# Custom_ST-Link_V3_0.net
KiCad netlist of a schematic drawn in Altium Designer
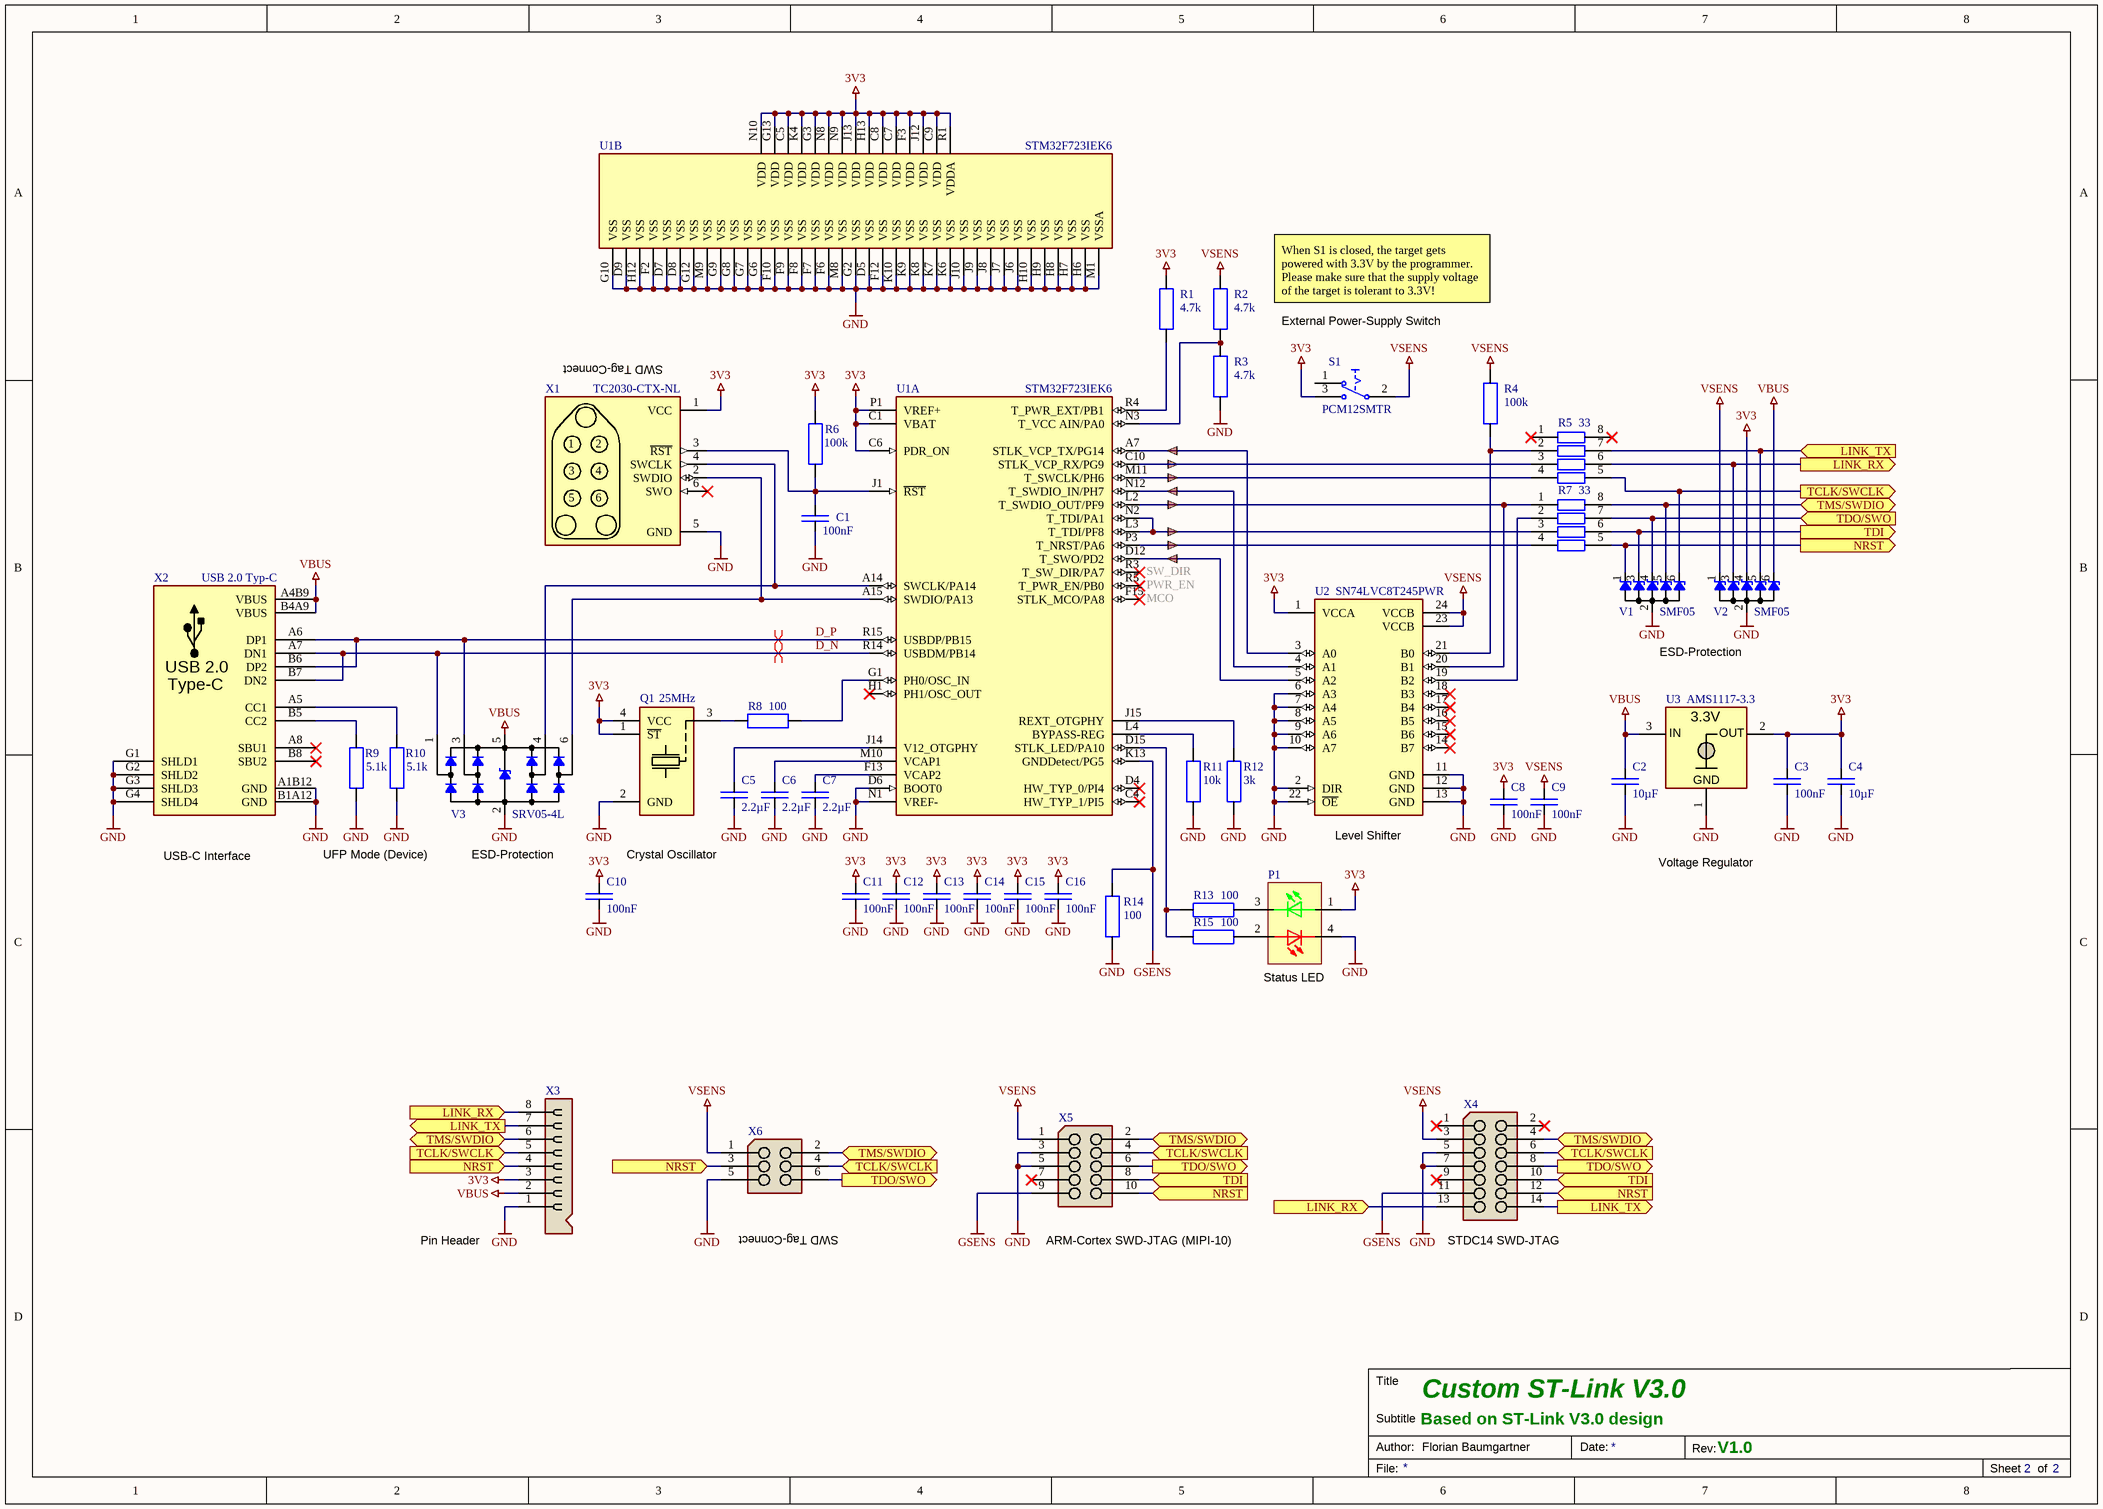
[diagram p0: Custom ST-Link V3.0.SchDoc]

(export (version "E")
  (design (tool "Eeschema 10.0.6"))
  (components
    (comp (ref "C1")
      (value "100nF")
      (footprint "SMD Keramikkondensator 0402")
      (description "CAP-MK")
      (libsource (lib "AudioAmp") (part "C-CAPACITOR"))
    )
    (comp (ref "C2")
      (value "10µF")
      (footprint "SMD Keramikkondensator 0603")
      (description "CAP-MK")
      (libsource (lib "AudioAmp") (part "C-CAPACITOR"))
    )
    (comp (ref "C3")
      (value "100nF")
      (footprint "SMD Keramikkondensator 0402")
      (description "CAP-MK")
      (libsource (lib "AudioAmp") (part "C-CAPACITOR"))
    )
    (comp (ref "C4")
      (value "10µF")
      (footprint "SMD Keramikkondensator 0603")
      (description "CAP-MK")
      (libsource (lib "AudioAmp") (part "C-CAPACITOR"))
    )
    (comp (ref "C5")
      (value "2.2µF")
      (footprint "SMD Keramikkondensator 0603")
      (description "CAP-MK")
      (libsource (lib "AudioAmp") (part "C-CAPACITOR"))
    )
    (comp (ref "C6")
      (value "2.2µF")
      (footprint "SMD Keramikkondensator 0603")
      (description "CAP-MK")
      (libsource (lib "AudioAmp") (part "C-CAPACITOR"))
    )
    (comp (ref "C7")
      (value "2.2µF")
      (footprint "SMD Keramikkondensator 0603")
      (description "CAP-MK")
      (libsource (lib "AudioAmp") (part "C-CAPACITOR"))
    )
    (comp (ref "C8")
      (value "100nF")
      (footprint "SMD Keramikkondensator 0402")
      (description "CAP-MK")
      (libsource (lib "AudioAmp") (part "C-CAPACITOR"))
    )
    (comp (ref "C9")
      (value "100nF")
      (footprint "SMD Keramikkondensator 0402")
      (description "CAP-MK")
      (libsource (lib "AudioAmp") (part "C-CAPACITOR"))
    )
    (comp (ref "C10")
      (value "100nF")
      (footprint "SMD Keramikkondensator 0402")
      (description "CAP-MK")
      (libsource (lib "AudioAmp") (part "C-CAPACITOR"))
    )
    (comp (ref "C11")
      (value "100nF")
      (footprint "SMD Keramikkondensator 0402")
      (description "CAP-MK")
      (libsource (lib "AudioAmp") (part "C-CAPACITOR"))
    )
    (comp (ref "C12")
      (value "100nF")
      (footprint "SMD Keramikkondensator 0402")
      (description "CAP-MK")
      (libsource (lib "AudioAmp") (part "C-CAPACITOR"))
    )
    (comp (ref "C13")
      (value "100nF")
      (footprint "SMD Keramikkondensator 0402")
      (description "CAP-MK")
      (libsource (lib "AudioAmp") (part "C-CAPACITOR"))
    )
    (comp (ref "C14")
      (value "100nF")
      (footprint "SMD Keramikkondensator 0402")
      (description "CAP-MK")
      (libsource (lib "AudioAmp") (part "C-CAPACITOR"))
    )
    (comp (ref "C15")
      (value "100nF")
      (footprint "SMD Keramikkondensator 0402")
      (description "CAP-MK")
      (libsource (lib "AudioAmp") (part "C-CAPACITOR"))
    )
    (comp (ref "C16")
      (value "100nF")
      (footprint "SMD Keramikkondensator 0402")
      (description "CAP-MK")
      (libsource (lib "AudioAmp") (part "C-CAPACITOR"))
    )
    (comp (ref "P1")
      (value "LTST-C155KGJRKT")
      (footprint "SMD LED 1210")
      (description "LED Red/Green")
      (libsource (lib "Custom ST-Link") (part "P-LTST-C155KGJRKT"))
    )
    (comp (ref "Q1")
      (value "25MHz")
      (footprint "SMD Crystal Oscillator 3.2X2.5X1.2")
      (description "Crystal Oscillator")
      (libsource (lib "Custom ST-Link") (part "Q-Oscillator"))
    )
    (comp (ref "R1")
      (value "4.7k")
      (footprint "SMD Widerstand 0402")
      (description "SMD-Widerstand 1/4W")
      (libsource (lib "Backplane_1") (part "R-RESISTOR"))
    )
    (comp (ref "R2")
      (value "4.7k")
      (footprint "SMD Widerstand 0402")
      (description "SMD-Widerstand 1/4W")
      (libsource (lib "Backplane_1") (part "R-RESISTOR"))
    )
    (comp (ref "R3")
      (value "4.7k")
      (footprint "SMD Widerstand 0402")
      (description "SMD-Widerstand 1/4W")
      (libsource (lib "Backplane_1") (part "R-RESISTOR"))
    )
    (comp (ref "R4")
      (value "100k")
      (footprint "SMD Widerstand 0402")
      (description "RES (E=Heizwiderstand B=Messwandler)")
      (libsource (lib "TFS Integrated Library") (part "R-RESISTOR"))
    )
    (comp (ref "R5")
      (value "33")
      (footprint "SMD Widerstand Array 4-Fach 0402")
      (description "Isolated Resistor Array")
      (libsource (lib "Custom ST-Link Old") (part "R-Array Single (4-Fach)"))
    )
    (comp (ref "R6")
      (value "100k")
      (footprint "SMD Widerstand 0402")
      (description "RES (E=Heizwiderstand B=Messwandler)")
      (libsource (lib "TFS Integrated Library") (part "R-RESISTOR"))
    )
    (comp (ref "R7")
      (value "33")
      (footprint "SMD Widerstand Array 4-Fach 0402")
      (description "Isolated Resistor Array")
      (libsource (lib "Custom ST-Link Old") (part "R-Array Single (4-Fach)"))
    )
    (comp (ref "R8")
      (value "100")
      (footprint "SMD Widerstand 0402")
      (description "SMD-Widerstand 1/4W")
      (libsource (lib "") (part "R-RESISTOR_1"))
    )
    (comp (ref "R9")
      (value "5.1k")
      (footprint "SMD Widerstand 0402")
      (description "SMD-Widerstand 1/4W")
      (libsource (lib "Backplane_1") (part "R-RESISTOR"))
    )
    (comp (ref "R10")
      (value "5.1k")
      (footprint "SMD Widerstand 0402")
      (description "SMD-Widerstand 1/4W")
      (libsource (lib "Backplane_1") (part "R-RESISTOR"))
    )
    (comp (ref "R11")
      (value "10k")
      (footprint "SMD Widerstand 0402")
      (description "RES (E=Heizwiderstand B=Messwandler)")
      (libsource (lib "TFS Integrated Library") (part "R-RESISTOR"))
    )
    (comp (ref "R12")
      (value "3k")
      (footprint "SMD Widerstand 0402")
      (description "SMD-Widerstand 1/4W")
      (libsource (lib "Backplane_1") (part "R-RESISTOR"))
    )
    (comp (ref "R13")
      (value "100")
      (footprint "SMD Widerstand 0402")
      (description "SMD-Widerstand 1/4W")
      (libsource (lib "Backplane_1") (part "R-RESISTOR"))
    )
    (comp (ref "R14")
      (value "100")
      (footprint "SMD Widerstand 0402")
      (description "SMD-Widerstand 1/4W")
      (libsource (lib "") (part "R-RESISTOR_2"))
    )
    (comp (ref "R15")
      (value "100")
      (footprint "SMD Widerstand 0402")
      (description "SMD-Widerstand 1/4W")
      (libsource (lib "Backplane_1") (part "R-RESISTOR"))
    )
    (comp (ref "S1")
      (value "PCM12SMTR")
      (footprint "SMD Switch SPDT (PCM12SMTR)")
      (description "Miniature Slide Switch")
      (libsource (lib "Custom ST-Link") (part "S-PCM12SMTR"))
    )
    (comp (ref "U1")
      (value "STM32F723IEK6")
      (description "ARM Cortex-M7 STM32F7 Microcontroller")
      (libsource (lib "Custom ST-Link") (part "U-STM32F723IEK6 (LINK V3E SWD)"))
    )
    (comp (ref "U2")
      (value "SN74LVC8T245PWR")
      (footprint "SMD IC TSSOP-24")
      (description "Octal dual supply translating transceiver")
      (libsource (lib "Custom ST-Link") (part "U-SN74LVC8T245PWR"))
    )
    (comp (ref "U3")
      (value "AMS1117-3.3")
      (footprint "SMD IC SOT-223")
      (description "LDO Voltage Regulator")
      (libsource (lib "Custom ST-Link Old") (part "T-AMS1117-3.3"))
    )
    (comp (ref "V1")
      (value "SMF05")
      (footprint "SMD IC SOT-363 (SC-70-6)")
      (description "Suppressor Diode Array")
      (libsource (lib "Custom ST-Link") (part "V-SMF05CT1G"))
    )
    (comp (ref "V2")
      (value "SMF05")
      (footprint "SMD IC SOT-363 (SC-70-6)")
      (description "Suppressor Diode Array")
      (libsource (lib "Custom ST-Link") (part "V-SMF05CT1G"))
    )
    (comp (ref "V3")
      (value "SRV05-4L")
      (footprint "SMD IC SOT-23-6")
      (description "Ultra Low Capacitance TVS Array")
      (libsource (lib "Custom ST-Link") (part "V-SRV05-4L-TP"))
    )
    (comp (ref "X1")
      (value "TC2030-CTX-NL")
      (footprint "SMD Connector TC2030-CTX-NL")
      (description "Tag-Connect for ARM-Cortex (6-Pin)")
      (libsource (lib "ZedBoard-Matrix Adapter") (part "X-TC2030-CTX-NL"))
    )
    (comp (ref "X2")
      (value "USB 2.0 Typ-C")
      (footprint "SMD USB-C Socket (A40-00119)")
      (description "Typ-C")
      (libsource (lib "Custom ST-Link") (part "X-USB-Buchse"))
    )
    (comp (ref "X3")
      (value "Buchsenleiste (8-Fach)")
      (footprint "SMD Buchsenleiste 8-Pol (1x8) 90°")
      (libsource (lib "Custom ST-Link Old") (part "X-Buchsenleiste (8-Fach)"))
    )
    (comp (ref "X4")
      (value "JTAG-Header (STDC14)")
      (footprint "SMD Connector 1.27mm (2x7)")
      (libsource (lib "Custom ST-Link Old") (part "X-JTAG-Header (STDC14)"))
    )
    (comp (ref "X5")
      (value "JTAG-Header (ARM-Cortex)")
      (footprint "SMD Connector 1.27mm (2x5)")
      (libsource (lib "Custom ST-Link Old") (part "X-JTAG-Header (ARM-Cortex)"))
    )
    (comp (ref "X6")
      (value "JTAG-Header (Tag-Connect)")
      (footprint "SMD Flachbandkabel 6-Pol Vertikal")
      (libsource (lib "Custom ST-Link Old") (part "X-JTAG-Header (Tag-Connect)"))
    )
  )
  (nets
    (net (code "1") (name "/D_N") (class "Default")
      (node (ref "U1") (pin "R14") (pinfunction "USBDM/PB14_R14") (pintype "bidirectional"))
      (node (ref "V3") (pin "1") (pinfunction "K_1") (pintype "passive"))
      (node (ref "X2") (pin "A7") (pinfunction "DN1_A7") (pintype "passive"))
      (node (ref "X2") (pin "B7") (pinfunction "DN2_B7") (pintype "passive"))
    )
    (net (code "2") (name "/D_P") (class "Default")
      (node (ref "U1") (pin "R15") (pinfunction "USBDP/PB15_R15") (pintype "bidirectional"))
      (node (ref "V3") (pin "3") (pinfunction "K_3") (pintype "passive"))
      (node (ref "X2") (pin "A6") (pinfunction "DP1_A6") (pintype "passive"))
      (node (ref "X2") (pin "B6") (pinfunction "DP2_B6") (pintype "passive"))
    )
    (net (code "3") (name "/LINK_RX") (class "Default")
      (node (ref "R5") (pin "6") (pinfunction "6_6") (pintype "passive"))
      (node (ref "V2") (pin "3") (pinfunction "K_3") (pintype "passive"))
      (node (ref "X3") (pin "8") (pinfunction "8_8") (pintype "passive"))
      (node (ref "X4") (pin "13") (pinfunction "13_13") (pintype "passive"))
    )
    (net (code "4") (name "/LINK_TX") (class "Default")
      (node (ref "R5") (pin "7") (pinfunction "7_7") (pintype "passive"))
      (node (ref "V2") (pin "5") (pinfunction "K_5") (pintype "passive"))
      (node (ref "X3") (pin "7") (pinfunction "7_7") (pintype "passive"))
      (node (ref "X4") (pin "14") (pinfunction "14_14") (pintype "passive"))
    )
    (net (code "5") (name "/NRST") (class "Default")
      (node (ref "R7") (pin "5") (pinfunction "5_5") (pintype "passive"))
      (node (ref "V1") (pin "1") (pinfunction "K_1") (pintype "passive"))
      (node (ref "X3") (pin "4") (pinfunction "4_4") (pintype "passive"))
      (node (ref "X4") (pin "12") (pinfunction "12_12") (pintype "passive"))
      (node (ref "X5") (pin "10") (pinfunction "10_10") (pintype "passive"))
      (node (ref "X6") (pin "3") (pinfunction "3_3") (pintype "passive"))
    )
    (net (code "6") (name "/TCLK{slash}SWCLK") (class "Default")
      (node (ref "R5") (pin "5") (pinfunction "5_5") (pintype "passive"))
      (node (ref "V1") (pin "6") (pinfunction "K_6") (pintype "passive"))
      (node (ref "X3") (pin "5") (pinfunction "5_5") (pintype "passive"))
      (node (ref "X4") (pin "6") (pinfunction "6_6") (pintype "passive"))
      (node (ref "X5") (pin "4") (pinfunction "4_4") (pintype "passive"))
      (node (ref "X6") (pin "4") (pinfunction "4_4") (pintype "passive"))
    )
    (net (code "7") (name "/TDI") (class "Default")
      (node (ref "R7") (pin "6") (pinfunction "6_6") (pintype "passive"))
      (node (ref "V1") (pin "3") (pinfunction "K_3") (pintype "passive"))
      (node (ref "X4") (pin "10") (pinfunction "10_10") (pintype "passive"))
      (node (ref "X5") (pin "8") (pinfunction "8_8") (pintype "passive"))
    )
    (net (code "8") (name "/TDO{slash}SWO") (class "Default")
      (node (ref "R7") (pin "7") (pinfunction "7_7") (pintype "passive"))
      (node (ref "V1") (pin "4") (pinfunction "K_4") (pintype "passive"))
      (node (ref "X4") (pin "8") (pinfunction "8_8") (pintype "passive"))
      (node (ref "X5") (pin "6") (pinfunction "6_6") (pintype "passive"))
      (node (ref "X6") (pin "6") (pinfunction "6_6") (pintype "passive"))
    )
    (net (code "9") (name "/TMS{slash}SWDIO") (class "Default")
      (node (ref "R7") (pin "8") (pinfunction "8_8") (pintype "passive"))
      (node (ref "V1") (pin "5") (pinfunction "K_5") (pintype "passive"))
      (node (ref "X3") (pin "6") (pinfunction "6_6") (pintype "passive"))
      (node (ref "X4") (pin "4") (pinfunction "4_4") (pintype "passive"))
      (node (ref "X5") (pin "2") (pinfunction "2_2") (pintype "passive"))
      (node (ref "X6") (pin "2") (pinfunction "2_2") (pintype "passive"))
    )
    (net (code "10") (name "3V3") (class "Default")
      (node (ref "C10") (pin "2") (pinfunction "2_2") (pintype "passive"))
      (node (ref "C11") (pin "2") (pinfunction "2_2") (pintype "passive"))
      (node (ref "C12") (pin "2") (pinfunction "2_2") (pintype "passive"))
      (node (ref "C13") (pin "2") (pinfunction "2_2") (pintype "passive"))
      (node (ref "C14") (pin "2") (pinfunction "2_2") (pintype "passive"))
      (node (ref "C15") (pin "2") (pinfunction "2_2") (pintype "passive"))
      (node (ref "C16") (pin "2") (pinfunction "2_2") (pintype "passive"))
      (node (ref "C3") (pin "2") (pinfunction "2_2") (pintype "passive"))
      (node (ref "C4") (pin "2") (pinfunction "2_2") (pintype "passive"))
      (node (ref "C8") (pin "2") (pinfunction "2_2") (pintype "passive"))
      (node (ref "P1") (pin "1") (pinfunction "GA_1") (pintype "passive"))
      (node (ref "Q1") (pin "1") (pinfunction "~{ST}_1") (pintype "passive"))
      (node (ref "Q1") (pin "4") (pinfunction "VCC_4") (pintype "passive"))
      (node (ref "R1") (pin "2") (pinfunction "2_2") (pintype "passive"))
      (node (ref "R6") (pin "2") (pinfunction "2_2") (pintype "passive"))
      (node (ref "S1") (pin "3") (pinfunction "NO1_3") (pintype "passive"))
      (node (ref "U1") (pin "C1") (pinfunction "VBAT_C1") (pintype "passive"))
      (node (ref "U1") (pin "C5") (pinfunction "VDD_C5") (pintype "power_in"))
      (node (ref "U1") (pin "C6") (pinfunction "PDR_ON_C6") (pintype "input"))
      (node (ref "U1") (pin "C7") (pinfunction "VDD_C7") (pintype "power_in"))
      (node (ref "U1") (pin "C8") (pinfunction "VDD_C8") (pintype "power_in"))
      (node (ref "U1") (pin "C9") (pinfunction "VDD_C9") (pintype "power_in"))
      (node (ref "U1") (pin "F3") (pinfunction "VDD_F3") (pintype "power_in"))
      (node (ref "U1") (pin "G13") (pinfunction "VDD_G13") (pintype "power_in"))
      (node (ref "U1") (pin "G3") (pinfunction "VDD_G3") (pintype "power_in"))
      (node (ref "U1") (pin "H13") (pinfunction "VDD_H13") (pintype "power_in"))
      (node (ref "U1") (pin "J12") (pinfunction "VDD_J12") (pintype "power_in"))
      (node (ref "U1") (pin "J13") (pinfunction "VDD_J13") (pintype "power_in"))
      (node (ref "U1") (pin "K4") (pinfunction "VDD_K4") (pintype "power_in"))
      (node (ref "U1") (pin "N10") (pinfunction "VDD_N10") (pintype "power_in"))
      (node (ref "U1") (pin "N8") (pinfunction "VDD_N8") (pintype "power_in"))
      (node (ref "U1") (pin "N9") (pinfunction "VDD_N9") (pintype "power_in"))
      (node (ref "U1") (pin "P1") (pinfunction "VREF+_P1") (pintype "passive"))
      (node (ref "U1") (pin "R1") (pinfunction "VDDA_R1") (pintype "power_in"))
      (node (ref "U2") (pin "1") (pinfunction "VCCA_1") (pintype "power_in"))
      (node (ref "U3") (pin "2") (pinfunction "OUT_2") (pintype "power_in"))
      (node (ref "V2") (pin "4") (pinfunction "K_4") (pintype "passive"))
      (node (ref "X1") (pin "1") (pinfunction "VCC_1") (pintype "power_in"))
      (node (ref "X3") (pin "3") (pinfunction "3_3") (pintype "passive"))
    )
    (net (code "11") (name "GND") (class "Default")
      (node (ref "C1") (pin "1") (pinfunction "1_1") (pintype "passive"))
      (node (ref "C10") (pin "1") (pinfunction "1_1") (pintype "passive"))
      (node (ref "C11") (pin "1") (pinfunction "1_1") (pintype "passive"))
      (node (ref "C12") (pin "1") (pinfunction "1_1") (pintype "passive"))
      (node (ref "C13") (pin "1") (pinfunction "1_1") (pintype "passive"))
      (node (ref "C14") (pin "1") (pinfunction "1_1") (pintype "passive"))
      (node (ref "C15") (pin "1") (pinfunction "1_1") (pintype "passive"))
      (node (ref "C16") (pin "1") (pinfunction "1_1") (pintype "passive"))
      (node (ref "C2") (pin "1") (pinfunction "1_1") (pintype "passive"))
      (node (ref "C3") (pin "1") (pinfunction "1_1") (pintype "passive"))
      (node (ref "C4") (pin "1") (pinfunction "1_1") (pintype "passive"))
      (node (ref "C5") (pin "1") (pinfunction "1_1") (pintype "passive"))
      (node (ref "C6") (pin "1") (pinfunction "1_1") (pintype "passive"))
      (node (ref "C7") (pin "1") (pinfunction "1_1") (pintype "passive"))
      (node (ref "C8") (pin "1") (pinfunction "1_1") (pintype "passive"))
      (node (ref "C9") (pin "1") (pinfunction "1_1") (pintype "passive"))
      (node (ref "P1") (pin "4") (pinfunction "RC_4") (pintype "passive"))
      (node (ref "Q1") (pin "2") (pinfunction "GND_2") (pintype "passive"))
      (node (ref "R10") (pin "1") (pinfunction "1_1") (pintype "passive"))
      (node (ref "R11") (pin "1") (pinfunction "1_1") (pintype "passive"))
      (node (ref "R12") (pin "1") (pinfunction "1_1") (pintype "passive"))
      (node (ref "R14") (pin "2") (pinfunction "2_2") (pintype "passive"))
      (node (ref "R3") (pin "1") (pinfunction "1_1") (pintype "passive"))
      (node (ref "R9") (pin "1") (pinfunction "1_1") (pintype "passive"))
      (node (ref "U1") (pin "D5") (pinfunction "VSS_D5") (pintype "power_in"))
      (node (ref "U1") (pin "D6") (pinfunction "BOOT0_D6") (pintype "input"))
      (node (ref "U1") (pin "D7") (pinfunction "VSS_D7") (pintype "power_in"))
      (node (ref "U1") (pin "D8") (pinfunction "VSS_D8") (pintype "power_in"))
      (node (ref "U1") (pin "D9") (pinfunction "VSS_D9") (pintype "power_in"))
      (node (ref "U1") (pin "F10") (pinfunction "VSS_F10") (pintype "power_in"))
      (node (ref "U1") (pin "F12") (pinfunction "VSS_F12") (pintype "power_in"))
      (node (ref "U1") (pin "F2") (pinfunction "VSS_F2") (pintype "power_in"))
      (node (ref "U1") (pin "F6") (pinfunction "VSS_F6") (pintype "power_in"))
      (node (ref "U1") (pin "F7") (pinfunction "VSS_F7") (pintype "power_in"))
      (node (ref "U1") (pin "F8") (pinfunction "VSS_F8") (pintype "power_in"))
      (node (ref "U1") (pin "F9") (pinfunction "VSS_F9") (pintype "power_in"))
      (node (ref "U1") (pin "G10") (pinfunction "VSS_G10") (pintype "power_in"))
      (node (ref "U1") (pin "G12") (pinfunction "VSS_G12") (pintype "power_in"))
      (node (ref "U1") (pin "G2") (pinfunction "VSS_G2") (pintype "power_in"))
      (node (ref "U1") (pin "G6") (pinfunction "VSS_G6") (pintype "power_in"))
      (node (ref "U1") (pin "G7") (pinfunction "VSS_G7") (pintype "power_in"))
      (node (ref "U1") (pin "G8") (pinfunction "VSS_G8") (pintype "power_in"))
      (node (ref "U1") (pin "G9") (pinfunction "VSS_G9") (pintype "power_in"))
      (node (ref "U1") (pin "H10") (pinfunction "VSS_H10") (pintype "power_in"))
      (node (ref "U1") (pin "H12") (pinfunction "VSS_H12") (pintype "power_in"))
      (node (ref "U1") (pin "H6") (pinfunction "VSS_H6") (pintype "power_in"))
      (node (ref "U1") (pin "H7") (pinfunction "VSS_H7") (pintype "power_in"))
      (node (ref "U1") (pin "H8") (pinfunction "VSS_H8") (pintype "power_in"))
      (node (ref "U1") (pin "H9") (pinfunction "VSS_H9") (pintype "power_in"))
      (node (ref "U1") (pin "J10") (pinfunction "VSS_J10") (pintype "power_in"))
      (node (ref "U1") (pin "J6") (pinfunction "VSS_J6") (pintype "power_in"))
      (node (ref "U1") (pin "J7") (pinfunction "VSS_J7") (pintype "power_in"))
      (node (ref "U1") (pin "J8") (pinfunction "VSS_J8") (pintype "power_in"))
      (node (ref "U1") (pin "J9") (pinfunction "VSS_J9") (pintype "power_in"))
      (node (ref "U1") (pin "K10") (pinfunction "VSS_K10") (pintype "power_in"))
      (node (ref "U1") (pin "K6") (pinfunction "VSS_K6") (pintype "power_in"))
      (node (ref "U1") (pin "K7") (pinfunction "VSS_K7") (pintype "power_in"))
      (node (ref "U1") (pin "K8") (pinfunction "VSS_K8") (pintype "power_in"))
      (node (ref "U1") (pin "K9") (pinfunction "VSS_K9") (pintype "power_in"))
      (node (ref "U1") (pin "M1") (pinfunction "VSSA_M1") (pintype "power_in"))
      (node (ref "U1") (pin "M8") (pinfunction "VSS_M8") (pintype "power_in"))
      (node (ref "U1") (pin "M9") (pinfunction "VSS_M9") (pintype "power_in"))
      (node (ref "U1") (pin "N1") (pinfunction "VREF-_N1") (pintype "passive"))
      (node (ref "U2") (pin "10") (pinfunction "A7_10") (pintype "bidirectional"))
      (node (ref "U2") (pin "11") (pinfunction "GND_11") (pintype "power_in"))
      (node (ref "U2") (pin "12") (pinfunction "GND_12") (pintype "power_in"))
      (node (ref "U2") (pin "13") (pinfunction "GND_13") (pintype "power_in"))
      (node (ref "U2") (pin "2") (pinfunction "DIR_2") (pintype "input"))
      (node (ref "U2") (pin "22") (pinfunction "~{OE}_22") (pintype "input"))
      (node (ref "U2") (pin "6") (pinfunction "A3_6") (pintype "bidirectional"))
      (node (ref "U2") (pin "7") (pinfunction "A4_7") (pintype "bidirectional"))
      (node (ref "U2") (pin "8") (pinfunction "A5_8") (pintype "bidirectional"))
      (node (ref "U2") (pin "9") (pinfunction "A6_9") (pintype "bidirectional"))
      (node (ref "U3") (pin "1") (pinfunction "GND_1") (pintype "power_in"))
      (node (ref "V1") (pin "2") (pinfunction "A_2") (pintype "passive"))
      (node (ref "V2") (pin "2") (pinfunction "A_2") (pintype "passive"))
      (node (ref "V3") (pin "2") (pinfunction "A_2") (pintype "passive"))
      (node (ref "X1") (pin "5") (pinfunction "GND_5") (pintype "power_in"))
      (node (ref "X2") (pin "A1B12") (pinfunction "GND_A1B12") (pintype "passive"))
      (node (ref "X2") (pin "B1A12") (pinfunction "GND_B1A12") (pintype "passive"))
      (node (ref "X2") (pin "G1") (pinfunction "SHLD1_G1") (pintype "passive"))
      (node (ref "X2") (pin "G2") (pinfunction "SHLD2_G2") (pintype "passive"))
      (node (ref "X2") (pin "G3") (pinfunction "SHLD3_G3") (pintype "passive"))
      (node (ref "X2") (pin "G4") (pinfunction "SHLD4_G4") (pintype "passive"))
      (node (ref "X3") (pin "1") (pinfunction "1_1") (pintype "passive"))
      (node (ref "X4") (pin "5") (pinfunction "5_5") (pintype "passive"))
      (node (ref "X4") (pin "7") (pinfunction "7_7") (pintype "passive"))
      (node (ref "X5") (pin "3") (pinfunction "3_3") (pintype "passive"))
      (node (ref "X5") (pin "5") (pinfunction "5_5") (pintype "passive"))
      (node (ref "X6") (pin "5") (pinfunction "5_5") (pintype "passive"))
    )
    (net (code "12") (name "GSENS") (class "Default")
      (node (ref "R14") (pin "1") (pinfunction "1_1") (pintype "passive"))
      (node (ref "U1") (pin "K13") (pinfunction "GNDDetect/PG5_K13") (pintype "bidirectional"))
      (node (ref "X4") (pin "11") (pinfunction "11_11") (pintype "passive"))
      (node (ref "X5") (pin "9") (pinfunction "9_9") (pintype "passive"))
    )
    (net (code "13") (name "Net-(P1-GC)") (class "Default")
      (node (ref "P1") (pin "3") (pinfunction "GC_3") (pintype "passive"))
      (node (ref "R13") (pin "2") (pinfunction "2_2") (pintype "passive"))
    )
    (net (code "14") (name "Net-(P1-RA)") (class "Default")
      (node (ref "P1") (pin "2") (pinfunction "RA_2") (pintype "passive"))
      (node (ref "R15") (pin "2") (pinfunction "2_2") (pintype "passive"))
    )
    (net (code "15") (name "Net-(Q1-OUT)") (class "Default")
      (node (ref "Q1") (pin "3") (pinfunction "OUT_3") (pintype "passive"))
      (node (ref "R8") (pin "2") (pinfunction "2_2") (pintype "passive"))
    )
    (net (code "16") (name "Net-(U1A-BYPASS-REG)") (class "Default")
      (node (ref "R11") (pin "2") (pinfunction "2_2") (pintype "passive"))
      (node (ref "U1") (pin "L4") (pinfunction "BYPASS-REG_L4") (pintype "passive"))
    )
    (net (code "17") (name "Net-(U1A-PH0{slash}OSC_IN)") (class "Default")
      (node (ref "R8") (pin "1") (pinfunction "1_1") (pintype "passive"))
      (node (ref "U1") (pin "G1") (pinfunction "PH0/OSC_IN_G1") (pintype "bidirectional"))
    )
    (net (code "18") (name "Net-(U1A-REXT_OTGPHY)") (class "Default")
      (node (ref "R12") (pin "2") (pinfunction "2_2") (pintype "passive"))
      (node (ref "U1") (pin "J15") (pinfunction "REXT_OTGPHY_J15") (pintype "passive"))
    )
    (net (code "19") (name "Net-(U1A-STLK_LED{slash}PA10)") (class "Default")
      (node (ref "R13") (pin "1") (pinfunction "1_1") (pintype "passive"))
      (node (ref "R15") (pin "1") (pinfunction "1_1") (pintype "passive"))
      (node (ref "U1") (pin "D15") (pinfunction "STLK_LED/PA10_D15") (pintype "bidirectional"))
    )
    (net (code "20") (name "Net-(U1A-STLK_VCP_RX{slash}PG9)") (class "Default")
      (node (ref "R5") (pin "3") (pinfunction "3_3") (pintype "passive"))
      (node (ref "U1") (pin "C10") (pinfunction "STLK_VCP_RX/PG9_C10") (pintype "bidirectional"))
    )
    (net (code "21") (name "Net-(U1A-STLK_VCP_TX{slash}PG14)") (class "Default")
      (node (ref "U1") (pin "A7") (pinfunction "STLK_VCP_TX/PG14_A7") (pintype "bidirectional"))
      (node (ref "U2") (pin "3") (pinfunction "A0_3") (pintype "bidirectional"))
    )
    (net (code "22") (name "Net-(U1A-SWCLK{slash}PA14)") (class "Default")
      (node (ref "U1") (pin "A14") (pinfunction "SWCLK/PA14_A14") (pintype "bidirectional"))
      (node (ref "V3") (pin "4") (pinfunction "K_4") (pintype "passive"))
      (node (ref "X1") (pin "4") (pinfunction "SWCLK_4") (pintype "output"))
    )
    (net (code "23") (name "Net-(U1A-SWDIO{slash}PA13)") (class "Default")
      (node (ref "U1") (pin "A15") (pinfunction "SWDIO/PA13_A15") (pintype "bidirectional"))
      (node (ref "V3") (pin "6") (pinfunction "K_6") (pintype "passive"))
      (node (ref "X1") (pin "2") (pinfunction "SWDIO_2") (pintype "bidirectional"))
    )
    (net (code "24") (name "Net-(U1A-T_NRST{slash}PA6)") (class "Default")
      (node (ref "R7") (pin "4") (pinfunction "4_4") (pintype "passive"))
      (node (ref "U1") (pin "P3") (pinfunction "T_NRST/PA6_P3") (pintype "bidirectional"))
    )
    (net (code "25") (name "Net-(U1A-T_PWR_EXT{slash}PB1)") (class "Default")
      (node (ref "R1") (pin "1") (pinfunction "1_1") (pintype "passive"))
      (node (ref "U1") (pin "R4") (pinfunction "T_PWR_EXT/PB1_R4") (pintype "bidirectional"))
    )
    (net (code "26") (name "Net-(U1A-T_SWCLK{slash}PH6)") (class "Default")
      (node (ref "R5") (pin "4") (pinfunction "4_4") (pintype "passive"))
      (node (ref "U1") (pin "M11") (pinfunction "T_SWCLK/PH6_M11") (pintype "bidirectional"))
    )
    (net (code "27") (name "Net-(U1A-T_SWDIO_IN{slash}PH7)") (class "Default")
      (node (ref "U1") (pin "N12") (pinfunction "T_SWDIO_IN/PH7_N12") (pintype "bidirectional"))
      (node (ref "U2") (pin "4") (pinfunction "A1_4") (pintype "bidirectional"))
    )
    (net (code "28") (name "Net-(U1A-T_SWDIO_OUT{slash}PF9)") (class "Default")
      (node (ref "R7") (pin "1") (pinfunction "1_1") (pintype "passive"))
      (node (ref "U1") (pin "L2") (pinfunction "T_SWDIO_OUT/PF9_L2") (pintype "bidirectional"))
      (node (ref "U2") (pin "20") (pinfunction "B1_20") (pintype "bidirectional"))
    )
    (net (code "29") (name "Net-(U1A-T_SWO{slash}PD2)") (class "Default")
      (node (ref "U1") (pin "D12") (pinfunction "T_SWO/PD2_D12") (pintype "bidirectional"))
      (node (ref "U2") (pin "5") (pinfunction "A2_5") (pintype "bidirectional"))
    )
    (net (code "30") (name "Net-(U1A-T_TDI{slash}PA1)") (class "Default")
      (node (ref "R7") (pin "3") (pinfunction "3_3") (pintype "passive"))
      (node (ref "U1") (pin "L3") (pinfunction "T_TDI/PF8_L3") (pintype "bidirectional"))
      (node (ref "U1") (pin "N2") (pinfunction "T_TDI/PA1_N2") (pintype "bidirectional"))
    )
    (net (code "31") (name "Net-(U1A-T_VCC_AIN{slash}PA0)") (class "Default")
      (node (ref "R2") (pin "1") (pinfunction "1_1") (pintype "passive"))
      (node (ref "R3") (pin "2") (pinfunction "2_2") (pintype "passive"))
      (node (ref "U1") (pin "N3") (pinfunction "T_VCC_AIN/PA0_N3") (pintype "bidirectional"))
    )
    (net (code "32") (name "Net-(U1A-V12_OTGPHY)") (class "Default")
      (node (ref "C5") (pin "2") (pinfunction "2_2") (pintype "passive"))
      (node (ref "U1") (pin "J14") (pinfunction "V12_OTGPHY_J14") (pintype "passive"))
    )
    (net (code "33") (name "Net-(U1A-VCAP1)") (class "Default")
      (node (ref "C6") (pin "2") (pinfunction "2_2") (pintype "passive"))
      (node (ref "U1") (pin "M10") (pinfunction "VCAP1_M10") (pintype "passive"))
    )
    (net (code "34") (name "Net-(U1A-VCAP2)") (class "Default")
      (node (ref "C7") (pin "2") (pinfunction "2_2") (pintype "passive"))
      (node (ref "U1") (pin "F13") (pinfunction "VCAP2_F13") (pintype "passive"))
    )
    (net (code "35") (name "Net-(U1A-~{RST})") (class "Default")
      (node (ref "C1") (pin "2") (pinfunction "2_2") (pintype "passive"))
      (node (ref "R6") (pin "1") (pinfunction "1_1") (pintype "passive"))
      (node (ref "U1") (pin "J1") (pinfunction "~{RST}_J1") (pintype "input"))
      (node (ref "X1") (pin "3") (pinfunction "~{RST}_3") (pintype "output"))
    )
    (net (code "36") (name "Net-(U2-B0)") (class "Default")
      (node (ref "R4") (pin "1") (pinfunction "1_1") (pintype "passive"))
      (node (ref "R5") (pin "2") (pinfunction "2_2") (pintype "passive"))
      (node (ref "U2") (pin "21") (pinfunction "B0_21") (pintype "bidirectional"))
    )
    (net (code "37") (name "Net-(U2-B2)") (class "Default")
      (node (ref "R7") (pin "2") (pinfunction "2_2") (pintype "passive"))
      (node (ref "U2") (pin "19") (pinfunction "B2_19") (pintype "bidirectional"))
    )
    (net (code "38") (name "Net-(X2-CC1)") (class "Default")
      (node (ref "R10") (pin "2") (pinfunction "2_2") (pintype "passive"))
      (node (ref "X2") (pin "A5") (pinfunction "CC1_A5") (pintype "passive"))
    )
    (net (code "39") (name "Net-(X2-CC2)") (class "Default")
      (node (ref "R9") (pin "2") (pinfunction "2_2") (pintype "passive"))
      (node (ref "X2") (pin "B5") (pinfunction "CC2_B5") (pintype "passive"))
    )
    (net (code "40") (name "VBUS") (class "Default")
      (node (ref "C2") (pin "2") (pinfunction "2_2") (pintype "passive"))
      (node (ref "U3") (pin "3") (pinfunction "IN_3") (pintype "power_in"))
      (node (ref "V2") (pin "6") (pinfunction "K_6") (pintype "passive"))
      (node (ref "V3") (pin "5") (pinfunction "K_5") (pintype "passive"))
      (node (ref "X2") (pin "A4B9") (pinfunction "VBUS_A4B9") (pintype "passive"))
      (node (ref "X2") (pin "B4A9") (pinfunction "VBUS_B4A9") (pintype "passive"))
      (node (ref "X3") (pin "2") (pinfunction "2_2") (pintype "passive"))
    )
    (net (code "41") (name "VSENS") (class "Default")
      (node (ref "C9") (pin "2") (pinfunction "2_2") (pintype "passive"))
      (node (ref "R2") (pin "2") (pinfunction "2_2") (pintype "passive"))
      (node (ref "R4") (pin "2") (pinfunction "2_2") (pintype "passive"))
      (node (ref "S1") (pin "2") (pinfunction "COMMON1_2") (pintype "passive"))
      (node (ref "U2") (pin "23") (pinfunction "VCCB_23") (pintype "power_in"))
      (node (ref "U2") (pin "24") (pinfunction "VCCB_24") (pintype "power_in"))
      (node (ref "V2") (pin "1") (pinfunction "K_1") (pintype "passive"))
      (node (ref "X4") (pin "3") (pinfunction "3_3") (pintype "passive"))
      (node (ref "X5") (pin "1") (pinfunction "1_1") (pintype "passive"))
      (node (ref "X6") (pin "1") (pinfunction "1_1") (pintype "passive"))
    )
    (net (code "42") (name "unconnected-(R5-Pad1)") (class "Default")
      (node (ref "R5") (pin "1") (pinfunction "1_1") (pintype "passive+no_connect"))
    )
    (net (code "43") (name "unconnected-(R5-Pad8)") (class "Default")
      (node (ref "R5") (pin "8") (pinfunction "8_8") (pintype "passive+no_connect"))
    )
    (net (code "44") (name "unconnected-(S1-NC1-Pad1)") (class "Default")
      (node (ref "S1") (pin "1") (pinfunction "NC1_1") (pintype "passive"))
    )
    (net (code "45") (name "unconnected-(U1A-HW_TYP_0{slash}PI4-PadD4)") (class "Default")
      (node (ref "U1") (pin "D4") (pinfunction "HW_TYP_0/PI4_D4") (pintype "bidirectional+no_connect"))
    )
    (net (code "46") (name "unconnected-(U1A-HW_TYP_1{slash}PI5-PadC4)") (class "Default")
      (node (ref "U1") (pin "C4") (pinfunction "HW_TYP_1/PI5_C4") (pintype "bidirectional+no_connect"))
    )
    (net (code "47") (name "unconnected-(U1A-PH1{slash}OSC_OUT-PadH1)") (class "Default")
      (node (ref "U1") (pin "H1") (pinfunction "PH1/OSC_OUT_H1") (pintype "bidirectional+no_connect"))
    )
    (net (code "48") (name "unconnected-(U1A-STLK_MCO{slash}PA8-PadF15)") (class "Default")
      (node (ref "U1") (pin "F15") (pinfunction "STLK_MCO/PA8_F15") (pintype "bidirectional+no_connect"))
    )
    (net (code "49") (name "unconnected-(U1A-T_PWR_EN{slash}PB0-PadR5)") (class "Default")
      (node (ref "U1") (pin "R5") (pinfunction "T_PWR_EN/PB0_R5") (pintype "bidirectional+no_connect"))
    )
    (net (code "50") (name "unconnected-(U1A-T_SW_DIR{slash}PA7-PadR3)") (class "Default")
      (node (ref "U1") (pin "R3") (pinfunction "T_SW_DIR/PA7_R3") (pintype "bidirectional+no_connect"))
    )
    (net (code "51") (name "unconnected-(U2-B3-Pad18)") (class "Default")
      (node (ref "U2") (pin "18") (pinfunction "B3_18") (pintype "bidirectional+no_connect"))
    )
    (net (code "52") (name "unconnected-(U2-B4-Pad17)") (class "Default")
      (node (ref "U2") (pin "17") (pinfunction "B4_17") (pintype "bidirectional+no_connect"))
    )
    (net (code "53") (name "unconnected-(U2-B5-Pad16)") (class "Default")
      (node (ref "U2") (pin "16") (pinfunction "B5_16") (pintype "bidirectional+no_connect"))
    )
    (net (code "54") (name "unconnected-(U2-B6-Pad15)") (class "Default")
      (node (ref "U2") (pin "15") (pinfunction "B6_15") (pintype "bidirectional+no_connect"))
    )
    (net (code "55") (name "unconnected-(U2-B7-Pad14)") (class "Default")
      (node (ref "U2") (pin "14") (pinfunction "B7_14") (pintype "bidirectional+no_connect"))
    )
    (net (code "56") (name "unconnected-(X1-SWO-Pad6)") (class "Default")
      (node (ref "X1") (pin "6") (pinfunction "SWO_6") (pintype "input+no_connect"))
    )
    (net (code "57") (name "unconnected-(X2-SBU1-PadA8)") (class "Default")
      (node (ref "X2") (pin "A8") (pinfunction "SBU1_A8") (pintype "passive+no_connect"))
    )
    (net (code "58") (name "unconnected-(X2-SBU2-PadB8)") (class "Default")
      (node (ref "X2") (pin "B8") (pinfunction "SBU2_B8") (pintype "passive+no_connect"))
    )
    (net (code "59") (name "unconnected-(X4-Pad1)") (class "Default")
      (node (ref "X4") (pin "1") (pinfunction "1_1") (pintype "passive+no_connect"))
    )
    (net (code "60") (name "unconnected-(X4-Pad2)") (class "Default")
      (node (ref "X4") (pin "2") (pinfunction "2_2") (pintype "passive+no_connect"))
    )
    (net (code "61") (name "unconnected-(X4-Pad9)") (class "Default")
      (node (ref "X4") (pin "9") (pinfunction "9_9") (pintype "passive+no_connect"))
    )
    (net (code "62") (name "unconnected-(X5-Pad7)") (class "Default")
      (node (ref "X5") (pin "7") (pinfunction "7_7") (pintype "passive+no_connect"))
    )
  )
)
